# BBB_Board.net
KiCad netlist of a schematic drawn in Altium Designer
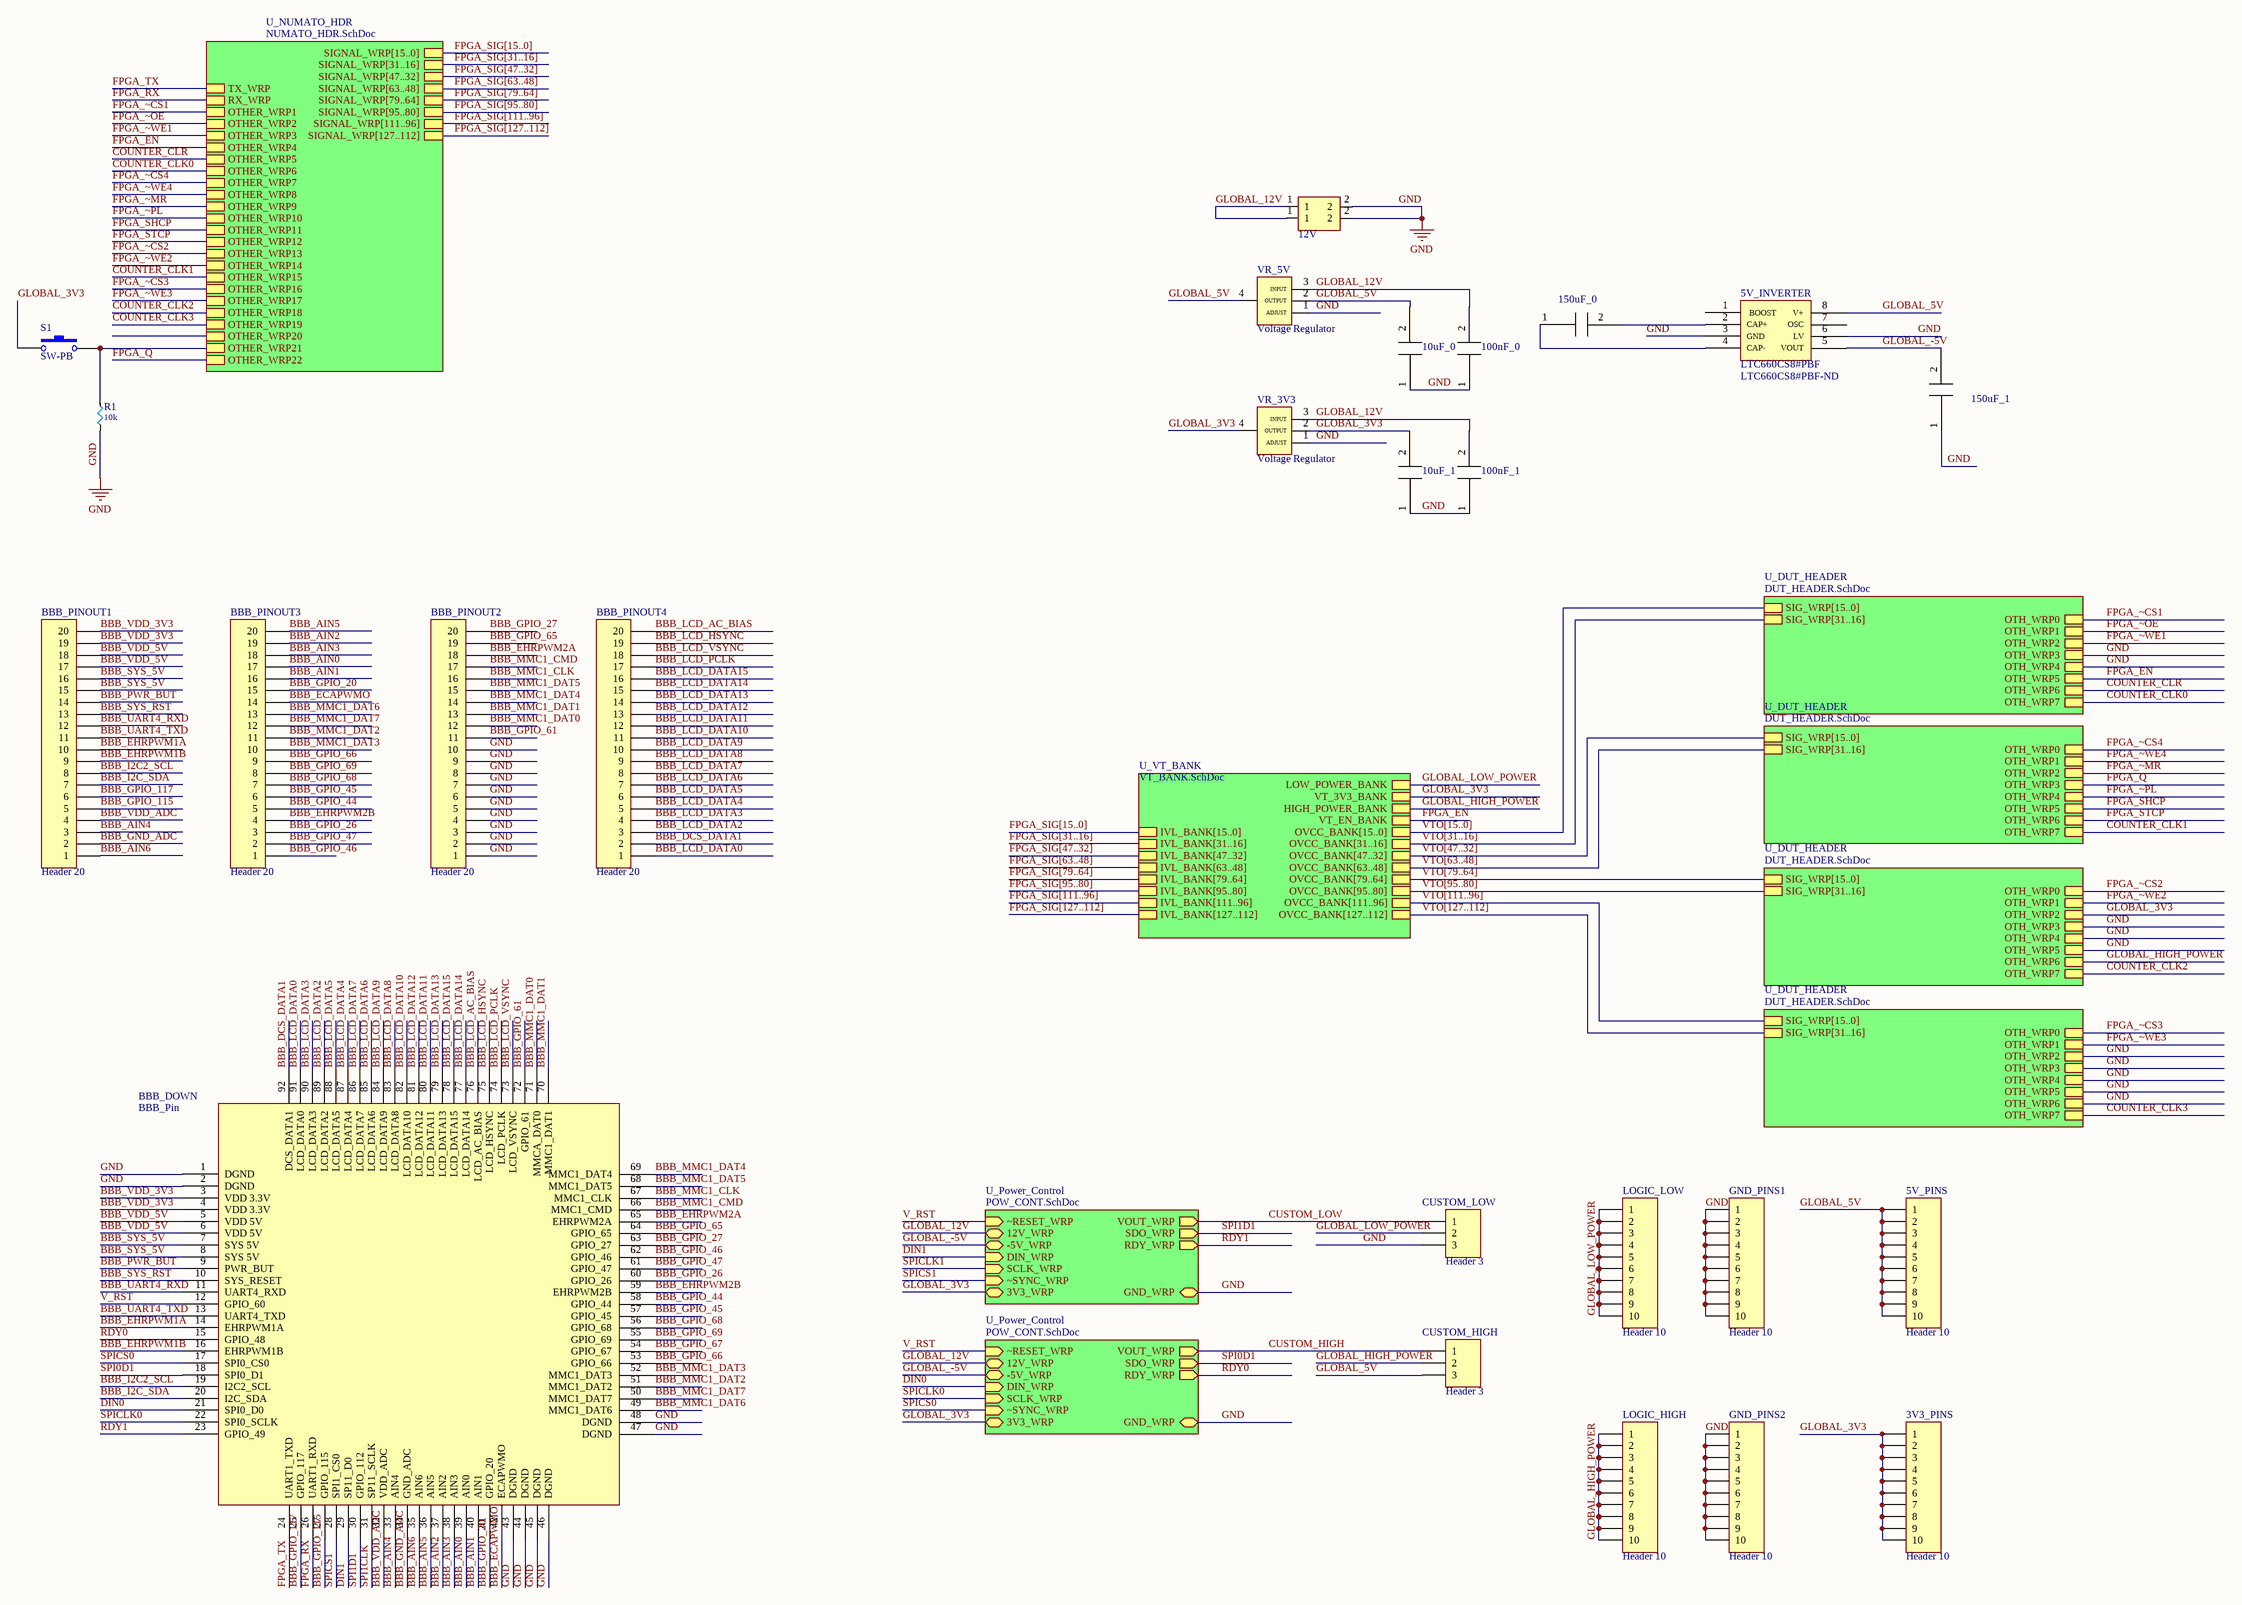
[diagram p0: BBB_Board.SchDoc]

(export (version "E")
  (design (tool "Eeschema 10.0.6"))
  (components
    (comp (ref "3V3_PINS")
      (value "Header 10")
      (footprint "HDR1X10")
      (description "Header, 10-Pin")
      (fields (field (name "PUBLISHER") "Altium Limited"))
      (libsource (lib "Miscellaneous Connectors") (part "Header 10"))
    )
    (comp (ref "5V_INVERTER")
      (value "LTC660CS8#PBF")
      (footprint "SOIC127P600X175-8N")
      (description "IC REG SWTCHD CAP INV 0.1A 8SOIC")
      (fields
        (field (name "MANUFACTURER") "Linear Technology")
        (field (name "SUPPLIER PART NUMBER 1") "LTC660CS8#PBF-ND")
      )
      (libsource (lib "BBB_Board") (part "LTC660CS8#PBF"))
    )
    (comp (ref "5V_PINS")
      (value "Header 10")
      (footprint "HDR1X10")
      (description "Header, 10-Pin")
      (fields (field (name "PUBLISHER") "Altium Limited"))
      (libsource (lib "Miscellaneous Connectors") (part "Header 10"))
    )
    (comp (ref "10uF_0")
      (value "0.1uF_0603")
      (footprint "0.1uF_0603")
      (libsource (lib "BBB_Board") (part "0.1uF_0603"))
    )
    (comp (ref "10uF_1")
      (value "0.1uF_0603")
      (footprint "0.1uF_0603")
      (libsource (lib "BBB_Board") (part "0.1uF_0603"))
    )
    (comp (ref "12V")
      (value "PJ-002BH-SMT-TR")
      (footprint "CP-002BHPJCT-ND")
      (description "CONN POWER JACK 2.5X5.5MM HI CUR")
      (fields (field (name "MANUFACTURER") "CUI Inc"))
      (libsource (lib "BBB_Board") (part "PJ-002BH-SMT-TR"))
    )
    (comp (ref "100nF_0")
      (value "0.1uF_0603")
      (footprint "0.1uF_0603")
      (libsource (lib "BBB_Board") (part "0.1uF_0603"))
    )
    (comp (ref "100nF_1")
      (value "0.1uF_0603")
      (footprint "0.1uF_0603")
      (libsource (lib "BBB_Board") (part "0.1uF_0603"))
    )
    (comp (ref "150uF_0")
      (value "0.1uF_0603")
      (footprint "0.1uF_0603")
      (libsource (lib "BBB_Board") (part "0.1uF_0603"))
    )
    (comp (ref "150uF_1")
      (value "0.1uF_0603")
      (footprint "0.1uF_0603")
      (libsource (lib "BBB_Board") (part "0.1uF_0603"))
    )
    (comp (ref "BBB_DOWN")
      (value "BBB_Pin")
      (footprint "BBB_Pin")
      (libsource (lib "BBB_Board") (part "BBB_Pin"))
    )
    (comp (ref "BBB_PINOUT1")
      (value "Header 20")
      (footprint "HDR1X20")
      (description "Header, 20-Pin")
      (fields (field (name "PUBLISHER") "Altium Limited"))
      (libsource (lib "Miscellaneous Connectors") (part "Header 20"))
    )
    (comp (ref "BBB_PINOUT2")
      (value "Header 20")
      (footprint "HDR1X20")
      (description "Header, 20-Pin")
      (fields (field (name "PUBLISHER") "Altium Limited"))
      (libsource (lib "Miscellaneous Connectors") (part "Header 20"))
    )
    (comp (ref "BBB_PINOUT3")
      (value "Header 20")
      (footprint "HDR1X20")
      (description "Header, 20-Pin")
      (fields (field (name "PUBLISHER") "Altium Limited"))
      (libsource (lib "Miscellaneous Connectors") (part "Header 20"))
    )
    (comp (ref "BBB_PINOUT4")
      (value "Header 20")
      (footprint "HDR1X20")
      (description "Header, 20-Pin")
      (fields (field (name "PUBLISHER") "Altium Limited"))
      (libsource (lib "Miscellaneous Connectors") (part "Header 20"))
    )
    (comp (ref "CUSTOM_HIGH")
      (value "Header 3")
      (footprint "HDR1X3")
      (description "Header, 3-Pin")
      (fields (field (name "PUBLISHER") "Altium Limited"))
      (libsource (lib "Miscellaneous Connectors") (part "Header 3"))
    )
    (comp (ref "CUSTOM_LOW")
      (value "Header 3")
      (footprint "HDR1X3")
      (description "Header, 3-Pin")
      (fields (field (name "PUBLISHER") "Altium Limited"))
      (libsource (lib "Miscellaneous Connectors") (part "Header 3"))
    )
    (comp (ref "GND_PINS1")
      (value "Header 10")
      (footprint "HDR1X10")
      (description "Header, 10-Pin")
      (fields (field (name "PUBLISHER") "Altium Limited"))
      (libsource (lib "Miscellaneous Connectors") (part "Header 10"))
    )
    (comp (ref "GND_PINS2")
      (value "Header 10")
      (footprint "HDR1X10")
      (description "Header, 10-Pin")
      (fields (field (name "PUBLISHER") "Altium Limited"))
      (libsource (lib "Miscellaneous Connectors") (part "Header 10"))
    )
    (comp (ref "LOGIC_HIGH")
      (value "Header 10")
      (footprint "HDR1X10")
      (description "Header, 10-Pin")
      (fields (field (name "PUBLISHER") "Altium Limited"))
      (libsource (lib "Miscellaneous Connectors") (part "Header 10"))
    )
    (comp (ref "LOGIC_LOW")
      (value "Header 10")
      (footprint "HDR1X10")
      (description "Header, 10-Pin")
      (fields (field (name "PUBLISHER") "Altium Limited"))
      (libsource (lib "Miscellaneous Connectors") (part "Header 10"))
    )
    (comp (ref "R1")
      (value "RNCS0603BKE10K0")
      (footprint "0.1uF_0603")
      (description "RES 10K OHM 1/16W 0.1% 0603")
      (fields
        (field (name "MANUFACTURER") "Stackpole Electronics Inc")
        (field (name "TOLERANCE") "±0.1%")
        (field (name "RESISTANCE (OHMS)") "10k")
      )
      (libsource (lib "BBB_Board") (part "RNCS0603BKE10K0"))
    )
    (comp (ref "S1")
      (value "SW-PB")
      (footprint "SPST-2")
      (description "Switch")
      (fields (field (name "PUBLISHER") "Altium Limited"))
      (libsource (lib "Miscellaneous Devices") (part "SW-PB"))
    )
    (comp (ref "VR_3V3")
      (value "Voltage Regulator")
      (footprint "volt_reg")
      (description "IC REG LDO ADJ 1.5A DDPAK")
      (fields
        (field (name "MANUFACTURER") "Texas Instruments")
        (field (name "MANUFACTURER PART NUMBER") "LM317KTTR")
      )
      (libsource (lib "BBB_Board") (part "Voltage Regulator"))
    )
    (comp (ref "VR_5V")
      (value "Voltage Regulator")
      (footprint "volt_reg")
      (description "IC REG LDO ADJ 1.5A DDPAK")
      (fields
        (field (name "MANUFACTURER") "Texas Instruments")
        (field (name "MANUFACTURER PART NUMBER") "LM317KTTR")
      )
      (libsource (lib "BBB_Board") (part "Voltage Regulator"))
    )
  )
  (nets
    (net (code "257") (name "/BBB_AIN0") (class "Default")
      (node (ref "BBB_DOWN") (pin "39") (pinfunction "AIN0_39") (pintype "passive"))
      (node (ref "BBB_PINOUT3") (pin "17") (pinfunction "17_17") (pintype "passive"))
    )
    (net (code "258") (name "/BBB_AIN1") (class "Default")
      (node (ref "BBB_DOWN") (pin "40") (pinfunction "AIN1_40") (pintype "passive"))
      (node (ref "BBB_PINOUT3") (pin "16") (pinfunction "16_16") (pintype "passive"))
    )
    (net (code "259") (name "/BBB_AIN2") (class "Default")
      (node (ref "BBB_DOWN") (pin "37") (pinfunction "AIN2_37") (pintype "passive"))
      (node (ref "BBB_PINOUT3") (pin "19") (pinfunction "19_19") (pintype "passive"))
    )
    (net (code "260") (name "/BBB_AIN3") (class "Default")
      (node (ref "BBB_DOWN") (pin "38") (pinfunction "AIN3_38") (pintype "passive"))
      (node (ref "BBB_PINOUT3") (pin "18") (pinfunction "18_18") (pintype "passive"))
    )
    (net (code "261") (name "/BBB_AIN4") (class "Default")
      (node (ref "BBB_DOWN") (pin "33") (pinfunction "AIN4_33") (pintype "passive"))
      (node (ref "BBB_PINOUT1") (pin "3") (pinfunction "3_3") (pintype "passive"))
    )
    (net (code "262") (name "/BBB_AIN5") (class "Default")
      (node (ref "BBB_DOWN") (pin "36") (pinfunction "AIN5_36") (pintype "passive"))
      (node (ref "BBB_PINOUT3") (pin "20") (pinfunction "20_20") (pintype "passive"))
    )
    (net (code "263") (name "/BBB_AIN6") (class "Default")
      (node (ref "BBB_DOWN") (pin "35") (pinfunction "AIN6_35") (pintype "passive"))
      (node (ref "BBB_PINOUT1") (pin "1") (pinfunction "1_1") (pintype "passive"))
    )
    (net (code "264") (name "/BBB_DCS_DATA1") (class "Default")
      (node (ref "BBB_DOWN") (pin "92") (pinfunction "DCS_DATA1_92") (pintype "passive"))
      (node (ref "BBB_PINOUT4") (pin "2") (pinfunction "2_2") (pintype "passive"))
    )
    (net (code "265") (name "/BBB_ECAPWMO") (class "Default")
      (node (ref "BBB_DOWN") (pin "42") (pinfunction "ECAPWMO_42") (pintype "passive"))
      (node (ref "BBB_PINOUT3") (pin "14") (pinfunction "14_14") (pintype "passive"))
    )
    (net (code "266") (name "/BBB_EHRPWM1A") (class "Default")
      (node (ref "BBB_DOWN") (pin "14") (pinfunction "EHRPWM1A_14") (pintype "passive"))
      (node (ref "BBB_PINOUT1") (pin "10") (pinfunction "10_10") (pintype "passive"))
    )
    (net (code "267") (name "/BBB_EHRPWM1B") (class "Default")
      (node (ref "BBB_DOWN") (pin "16") (pinfunction "EHRPWM1B_16") (pintype "passive"))
      (node (ref "BBB_PINOUT1") (pin "9") (pinfunction "9_9") (pintype "passive"))
    )
    (net (code "268") (name "/BBB_EHRPWM2A") (class "Default")
      (node (ref "BBB_DOWN") (pin "65") (pinfunction "EHRPWM2A_65") (pintype "passive"))
      (node (ref "BBB_PINOUT2") (pin "18") (pinfunction "18_18") (pintype "passive"))
    )
    (net (code "269") (name "/BBB_EHRPWM2B") (class "Default")
      (node (ref "BBB_DOWN") (pin "59") (pinfunction "EHRPWM2B_59") (pintype "passive"))
      (node (ref "BBB_PINOUT3") (pin "4") (pinfunction "4_4") (pintype "passive"))
    )
    (net (code "270") (name "/BBB_GND_ADC") (class "Default")
      (node (ref "BBB_DOWN") (pin "34") (pinfunction "GND_ADC_34") (pintype "passive"))
      (node (ref "BBB_PINOUT1") (pin "2") (pinfunction "2_2") (pintype "passive"))
    )
    (net (code "271") (name "/BBB_GPIO_20") (class "Default")
      (node (ref "BBB_DOWN") (pin "41") (pinfunction "GPIO_20_41") (pintype "passive"))
      (node (ref "BBB_PINOUT3") (pin "15") (pinfunction "15_15") (pintype "passive"))
    )
    (net (code "272") (name "/BBB_GPIO_26") (class "Default")
      (node (ref "BBB_DOWN") (pin "60") (pinfunction "GPIO_26_60") (pintype "passive"))
      (node (ref "BBB_PINOUT3") (pin "3") (pinfunction "3_3") (pintype "passive"))
    )
    (net (code "273") (name "/BBB_GPIO_27") (class "Default")
      (node (ref "BBB_DOWN") (pin "63") (pinfunction "GPIO_27_63") (pintype "passive"))
      (node (ref "BBB_PINOUT2") (pin "20") (pinfunction "20_20") (pintype "passive"))
    )
    (net (code "274") (name "/BBB_GPIO_44") (class "Default")
      (node (ref "BBB_DOWN") (pin "58") (pinfunction "GPIO_44_58") (pintype "passive"))
      (node (ref "BBB_PINOUT3") (pin "5") (pinfunction "5_5") (pintype "passive"))
    )
    (net (code "275") (name "/BBB_GPIO_45") (class "Default")
      (node (ref "BBB_DOWN") (pin "57") (pinfunction "GPIO_45_57") (pintype "passive"))
      (node (ref "BBB_PINOUT3") (pin "6") (pinfunction "6_6") (pintype "passive"))
    )
    (net (code "276") (name "/BBB_GPIO_46") (class "Default")
      (node (ref "BBB_DOWN") (pin "62") (pinfunction "GPIO_46_62") (pintype "passive"))
      (node (ref "BBB_PINOUT3") (pin "1") (pinfunction "1_1") (pintype "passive"))
    )
    (net (code "277") (name "/BBB_GPIO_47") (class "Default")
      (node (ref "BBB_DOWN") (pin "61") (pinfunction "GPIO_47_61") (pintype "passive"))
      (node (ref "BBB_PINOUT3") (pin "2") (pinfunction "2_2") (pintype "passive"))
    )
    (net (code "278") (name "/BBB_GPIO_61") (class "Default")
      (node (ref "BBB_DOWN") (pin "72") (pinfunction "GPIO_61_72") (pintype "passive"))
      (node (ref "BBB_PINOUT2") (pin "11") (pinfunction "11_11") (pintype "passive"))
    )
    (net (code "279") (name "/BBB_GPIO_65") (class "Default")
      (node (ref "BBB_DOWN") (pin "64") (pinfunction "GPIO_65_64") (pintype "passive"))
      (node (ref "BBB_PINOUT2") (pin "19") (pinfunction "19_19") (pintype "passive"))
    )
    (net (code "280") (name "/BBB_GPIO_66") (class "Default")
      (node (ref "BBB_DOWN") (pin "53") (pinfunction "GPIO_66_53") (pintype "passive"))
      (node (ref "BBB_PINOUT3") (pin "9") (pinfunction "9_9") (pintype "passive"))
    )
    (net (code "281") (name "/BBB_GPIO_67") (class "Default")
      (node (ref "BBB_DOWN") (pin "54") (pinfunction "GPIO_67_54") (pintype "passive"))
    )
    (net (code "282") (name "/BBB_GPIO_68") (class "Default")
      (node (ref "BBB_DOWN") (pin "56") (pinfunction "GPIO_68_56") (pintype "passive"))
      (node (ref "BBB_PINOUT3") (pin "7") (pinfunction "7_7") (pintype "passive"))
    )
    (net (code "283") (name "/BBB_GPIO_69") (class "Default")
      (node (ref "BBB_DOWN") (pin "55") (pinfunction "GPIO_69_55") (pintype "passive"))
      (node (ref "BBB_PINOUT3") (pin "8") (pinfunction "8_8") (pintype "passive"))
    )
    (net (code "284") (name "/BBB_GPIO_115") (class "Default")
      (node (ref "BBB_DOWN") (pin "27") (pinfunction "GPIO_115_27") (pintype "passive"))
      (node (ref "BBB_PINOUT1") (pin "5") (pinfunction "5_5") (pintype "passive"))
    )
    (net (code "285") (name "/BBB_GPIO_117") (class "Default")
      (node (ref "BBB_DOWN") (pin "25") (pinfunction "GPIO_117_25") (pintype "passive"))
      (node (ref "BBB_PINOUT1") (pin "6") (pinfunction "6_6") (pintype "passive"))
    )
    (net (code "286") (name "/BBB_I2C2_SCL") (class "Default")
      (node (ref "BBB_DOWN") (pin "19") (pinfunction "I2C2_SCL_19") (pintype "passive"))
      (node (ref "BBB_PINOUT1") (pin "8") (pinfunction "8_8") (pintype "passive"))
    )
    (net (code "287") (name "/BBB_I2C_SDA") (class "Default")
      (node (ref "BBB_DOWN") (pin "20") (pinfunction "I2C_SDA_20") (pintype "passive"))
      (node (ref "BBB_PINOUT1") (pin "7") (pinfunction "7_7") (pintype "passive"))
    )
    (net (code "288") (name "/BBB_LCD_AC_BIAS") (class "Default")
      (node (ref "BBB_DOWN") (pin "76") (pinfunction "LCD_AC_BIAS_76") (pintype "passive"))
      (node (ref "BBB_PINOUT4") (pin "20") (pinfunction "20_20") (pintype "passive"))
    )
    (net (code "289") (name "/BBB_LCD_DATA0") (class "Default")
      (node (ref "BBB_DOWN") (pin "91") (pinfunction "LCD_DATA0_91") (pintype "passive"))
      (node (ref "BBB_PINOUT4") (pin "1") (pinfunction "1_1") (pintype "passive"))
    )
    (net (code "290") (name "/BBB_LCD_DATA2") (class "Default")
      (node (ref "BBB_DOWN") (pin "89") (pinfunction "LCD_DATA2_89") (pintype "passive"))
      (node (ref "BBB_PINOUT4") (pin "3") (pinfunction "3_3") (pintype "passive"))
    )
    (net (code "291") (name "/BBB_LCD_DATA3") (class "Default")
      (node (ref "BBB_DOWN") (pin "90") (pinfunction "LCD_DATA3_90") (pintype "passive"))
      (node (ref "BBB_PINOUT4") (pin "4") (pinfunction "4_4") (pintype "passive"))
    )
    (net (code "292") (name "/BBB_LCD_DATA4") (class "Default")
      (node (ref "BBB_DOWN") (pin "87") (pinfunction "LCD_DATA4_87") (pintype "passive"))
      (node (ref "BBB_PINOUT4") (pin "5") (pinfunction "5_5") (pintype "passive"))
    )
    (net (code "293") (name "/BBB_LCD_DATA5") (class "Default")
      (node (ref "BBB_DOWN") (pin "88") (pinfunction "LCD_DATA5_88") (pintype "passive"))
      (node (ref "BBB_PINOUT4") (pin "6") (pinfunction "6_6") (pintype "passive"))
    )
    (net (code "294") (name "/BBB_LCD_DATA6") (class "Default")
      (node (ref "BBB_DOWN") (pin "85") (pinfunction "LCD_DATA6_85") (pintype "passive"))
      (node (ref "BBB_PINOUT4") (pin "7") (pinfunction "7_7") (pintype "passive"))
    )
    (net (code "295") (name "/BBB_LCD_DATA7") (class "Default")
      (node (ref "BBB_DOWN") (pin "86") (pinfunction "LCD_DATA7_86") (pintype "passive"))
      (node (ref "BBB_PINOUT4") (pin "8") (pinfunction "8_8") (pintype "passive"))
    )
    (net (code "296") (name "/BBB_LCD_DATA8") (class "Default")
      (node (ref "BBB_DOWN") (pin "83") (pinfunction "LCD_DATA8_83") (pintype "passive"))
      (node (ref "BBB_PINOUT4") (pin "9") (pinfunction "9_9") (pintype "passive"))
    )
    (net (code "297") (name "/BBB_LCD_DATA9") (class "Default")
      (node (ref "BBB_DOWN") (pin "84") (pinfunction "LCD_DATA9_84") (pintype "passive"))
      (node (ref "BBB_PINOUT4") (pin "10") (pinfunction "10_10") (pintype "passive"))
    )
    (net (code "298") (name "/BBB_LCD_DATA10") (class "Default")
      (node (ref "BBB_DOWN") (pin "82") (pinfunction "LCD_DATA10_82") (pintype "passive"))
      (node (ref "BBB_PINOUT4") (pin "11") (pinfunction "11_11") (pintype "passive"))
    )
    (net (code "299") (name "/BBB_LCD_DATA11") (class "Default")
      (node (ref "BBB_DOWN") (pin "80") (pinfunction "LCD_DATA11_80") (pintype "passive"))
      (node (ref "BBB_PINOUT4") (pin "12") (pinfunction "12_12") (pintype "passive"))
    )
    (net (code "300") (name "/BBB_LCD_DATA12") (class "Default")
      (node (ref "BBB_DOWN") (pin "81") (pinfunction "LCD_DATA12_81") (pintype "passive"))
      (node (ref "BBB_PINOUT4") (pin "13") (pinfunction "13_13") (pintype "passive"))
    )
    (net (code "301") (name "/BBB_LCD_DATA13") (class "Default")
      (node (ref "BBB_DOWN") (pin "79") (pinfunction "LCD_DATA13_79") (pintype "passive"))
      (node (ref "BBB_PINOUT4") (pin "14") (pinfunction "14_14") (pintype "passive"))
    )
    (net (code "302") (name "/BBB_LCD_DATA14") (class "Default")
      (node (ref "BBB_DOWN") (pin "77") (pinfunction "LCD_DATA14_77") (pintype "passive"))
      (node (ref "BBB_PINOUT4") (pin "15") (pinfunction "15_15") (pintype "passive"))
    )
    (net (code "303") (name "/BBB_LCD_DATA15") (class "Default")
      (node (ref "BBB_DOWN") (pin "78") (pinfunction "LCD_DATA15_78") (pintype "passive"))
      (node (ref "BBB_PINOUT4") (pin "16") (pinfunction "16_16") (pintype "passive"))
    )
    (net (code "304") (name "/BBB_LCD_HSYNC") (class "Default")
      (node (ref "BBB_DOWN") (pin "75") (pinfunction "LCD_HSYNC_75") (pintype "passive"))
      (node (ref "BBB_PINOUT4") (pin "19") (pinfunction "19_19") (pintype "passive"))
    )
    (net (code "305") (name "/BBB_LCD_PCLK") (class "Default")
      (node (ref "BBB_DOWN") (pin "74") (pinfunction "LCD_PCLK_74") (pintype "passive"))
      (node (ref "BBB_PINOUT4") (pin "17") (pinfunction "17_17") (pintype "passive"))
    )
    (net (code "306") (name "/BBB_LCD_VSYNC") (class "Default")
      (node (ref "BBB_DOWN") (pin "73") (pinfunction "LCD_VSYNC_73") (pintype "passive"))
      (node (ref "BBB_PINOUT4") (pin "18") (pinfunction "18_18") (pintype "passive"))
    )
    (net (code "307") (name "/BBB_MMC1_CLK") (class "Default")
      (node (ref "BBB_DOWN") (pin "67") (pinfunction "MMC1_CLK_67") (pintype "passive"))
      (node (ref "BBB_PINOUT2") (pin "16") (pinfunction "16_16") (pintype "passive"))
    )
    (net (code "308") (name "/BBB_MMC1_CMD") (class "Default")
      (node (ref "BBB_DOWN") (pin "66") (pinfunction "MMC1_CMD_66") (pintype "passive"))
      (node (ref "BBB_PINOUT2") (pin "17") (pinfunction "17_17") (pintype "passive"))
    )
    (net (code "309") (name "/BBB_MMC1_DAT0") (class "Default")
      (node (ref "BBB_DOWN") (pin "71") (pinfunction "MMCA_DAT0_71") (pintype "passive"))
      (node (ref "BBB_PINOUT2") (pin "12") (pinfunction "12_12") (pintype "passive"))
    )
    (net (code "310") (name "/BBB_MMC1_DAT1") (class "Default")
      (node (ref "BBB_DOWN") (pin "70") (pinfunction "MMC1_DAT1_70") (pintype "passive"))
      (node (ref "BBB_PINOUT2") (pin "13") (pinfunction "13_13") (pintype "passive"))
    )
    (net (code "311") (name "/BBB_MMC1_DAT2") (class "Default")
      (node (ref "BBB_DOWN") (pin "51") (pinfunction "MMC1_DAT2_51") (pintype "passive"))
      (node (ref "BBB_PINOUT3") (pin "11") (pinfunction "11_11") (pintype "passive"))
    )
    (net (code "312") (name "/BBB_MMC1_DAT3") (class "Default")
      (node (ref "BBB_DOWN") (pin "52") (pinfunction "MMC1_DAT3_52") (pintype "passive"))
      (node (ref "BBB_PINOUT3") (pin "10") (pinfunction "10_10") (pintype "passive"))
    )
    (net (code "313") (name "/BBB_MMC1_DAT4") (class "Default")
      (node (ref "BBB_DOWN") (pin "69") (pinfunction "MMC1_DAT4_69") (pintype "passive"))
      (node (ref "BBB_PINOUT2") (pin "14") (pinfunction "14_14") (pintype "passive"))
    )
    (net (code "314") (name "/BBB_MMC1_DAT5") (class "Default")
      (node (ref "BBB_DOWN") (pin "68") (pinfunction "MMC1_DAT5_68") (pintype "passive"))
      (node (ref "BBB_PINOUT2") (pin "15") (pinfunction "15_15") (pintype "passive"))
    )
    (net (code "315") (name "/BBB_MMC1_DAT6") (class "Default")
      (node (ref "BBB_DOWN") (pin "49") (pinfunction "MMC1_DAT6_49") (pintype "passive"))
      (node (ref "BBB_PINOUT3") (pin "13") (pinfunction "13_13") (pintype "passive"))
    )
    (net (code "316") (name "/BBB_MMC1_DAT7") (class "Default")
      (node (ref "BBB_DOWN") (pin "50") (pinfunction "MMC1_DAT7_50") (pintype "passive"))
      (node (ref "BBB_PINOUT3") (pin "12") (pinfunction "12_12") (pintype "passive"))
    )
    (net (code "317") (name "/BBB_PWR_BUT") (class "Default")
      (node (ref "BBB_DOWN") (pin "9") (pinfunction "PWR_BUT_9") (pintype "passive"))
      (node (ref "BBB_PINOUT1") (pin "14") (pinfunction "14_14") (pintype "passive"))
    )
    (net (code "318") (name "/BBB_SYS_5V") (class "Default")
      (node (ref "BBB_DOWN") (pin "7") (pinfunction "SYS_5V_7") (pintype "passive"))
      (node (ref "BBB_DOWN") (pin "8") (pinfunction "SYS_5V_8") (pintype "passive"))
      (node (ref "BBB_PINOUT1") (pin "15") (pinfunction "15_15") (pintype "passive"))
      (node (ref "BBB_PINOUT1") (pin "16") (pinfunction "16_16") (pintype "passive"))
    )
    (net (code "319") (name "/BBB_SYS_RST") (class "Default")
      (node (ref "BBB_DOWN") (pin "10") (pinfunction "SYS_RESET_10") (pintype "passive"))
      (node (ref "BBB_PINOUT1") (pin "13") (pinfunction "13_13") (pintype "passive"))
    )
    (net (code "320") (name "/BBB_UART4_RXD") (class "Default")
      (node (ref "BBB_DOWN") (pin "11") (pinfunction "UART4_RXD_11") (pintype "passive"))
      (node (ref "BBB_PINOUT1") (pin "12") (pinfunction "12_12") (pintype "passive"))
    )
    (net (code "321") (name "/BBB_UART4_TXD") (class "Default")
      (node (ref "BBB_DOWN") (pin "13") (pinfunction "UART4_TXD_13") (pintype "passive"))
      (node (ref "BBB_PINOUT1") (pin "11") (pinfunction "11_11") (pintype "passive"))
    )
    (net (code "322") (name "/BBB_VDD_3V3") (class "Default")
      (node (ref "BBB_DOWN") (pin "3") (pinfunction "VDD_3.3V_3") (pintype "passive"))
      (node (ref "BBB_DOWN") (pin "4") (pinfunction "VDD_3.3V_4") (pintype "passive"))
      (node (ref "BBB_PINOUT1") (pin "19") (pinfunction "19_19") (pintype "passive"))
      (node (ref "BBB_PINOUT1") (pin "20") (pinfunction "20_20") (pintype "passive"))
    )
    (net (code "323") (name "/BBB_VDD_5V") (class "Default")
      (node (ref "BBB_DOWN") (pin "5") (pinfunction "VDD_5V_5") (pintype "passive"))
      (node (ref "BBB_DOWN") (pin "6") (pinfunction "VDD_5V_6") (pintype "passive"))
      (node (ref "BBB_PINOUT1") (pin "17") (pinfunction "17_17") (pintype "passive"))
      (node (ref "BBB_PINOUT1") (pin "18") (pinfunction "18_18") (pintype "passive"))
    )
    (net (code "324") (name "/BBB_VDD_ADC") (class "Default")
      (node (ref "BBB_DOWN") (pin "32") (pinfunction "VDD_ADC_32") (pintype "passive"))
      (node (ref "BBB_PINOUT1") (pin "4") (pinfunction "4_4") (pintype "passive"))
    )
    (net (code "330") (name "/CUSTOM_HIGH") (class "Default")
      (node (ref "CUSTOM_HIGH") (pin "1") (pinfunction "1_1") (pintype "passive"))
    )
    (net (code "331") (name "/CUSTOM_LOW") (class "Default")
      (node (ref "CUSTOM_LOW") (pin "1") (pinfunction "1_1") (pintype "passive"))
    )
    (net (code "332") (name "/DIN0") (class "Default")
      (node (ref "BBB_DOWN") (pin "21") (pinfunction "SPI0_D0_21") (pintype "passive"))
    )
    (net (code "333") (name "/DIN1") (class "Default")
      (node (ref "BBB_DOWN") (pin "29") (pinfunction "SP11_D0_29") (pintype "passive"))
    )
    (net (code "336") (name "/FPGA_RX") (class "Default")
      (node (ref "BBB_DOWN") (pin "26") (pinfunction "UART1_RXD_26") (pintype "passive"))
    )
    (net (code "347") (name "/FPGA_TX") (class "Default")
      (node (ref "BBB_DOWN") (pin "24") (pinfunction "UART1_TXD_24") (pintype "passive"))
    )
    (net (code "359") (name "/GLOBAL_-5V") (class "Default")
      (node (ref "150uF_1") (pin "2") (pinfunction "2_2") (pintype "passive"))
      (node (ref "5V_INVERTER") (pin "5") (pinfunction "VOUT_5") (pintype "passive"))
    )
    (net (code "360") (name "/GLOBAL_3V3") (class "Default")
      (node (ref "10uF_1") (pin "2") (pinfunction "2_2") (pintype "passive"))
      (node (ref "3V3_PINS") (pin "1") (pinfunction "1_1") (pintype "passive"))
      (node (ref "3V3_PINS") (pin "10") (pinfunction "10_10") (pintype "passive"))
      (node (ref "3V3_PINS") (pin "2") (pinfunction "2_2") (pintype "passive"))
      (node (ref "3V3_PINS") (pin "3") (pinfunction "3_3") (pintype "passive"))
      (node (ref "3V3_PINS") (pin "4") (pinfunction "4_4") (pintype "passive"))
      (node (ref "3V3_PINS") (pin "5") (pinfunction "5_5") (pintype "passive"))
      (node (ref "3V3_PINS") (pin "6") (pinfunction "6_6") (pintype "passive"))
      (node (ref "3V3_PINS") (pin "7") (pinfunction "7_7") (pintype "passive"))
      (node (ref "3V3_PINS") (pin "8") (pinfunction "8_8") (pintype "passive"))
      (node (ref "3V3_PINS") (pin "9") (pinfunction "9_9") (pintype "passive"))
      (node (ref "S1") (pin "1") (pinfunction "1_1") (pintype "passive"))
      (node (ref "VR_3V3") (pin "2") (pinfunction "OUTPUT_2") (pintype "passive"))
      (node (ref "VR_3V3") (pin "4") (pinfunction "Output_4") (pintype "passive"))
    )
    (net (code "361") (name "/GLOBAL_5V") (class "Default")
      (node (ref "10uF_0") (pin "2") (pinfunction "2_2") (pintype "passive"))
      (node (ref "5V_INVERTER") (pin "8") (pinfunction "V+_8") (pintype "passive"))
      (node (ref "5V_PINS") (pin "1") (pinfunction "1_1") (pintype "passive"))
      (node (ref "5V_PINS") (pin "10") (pinfunction "10_10") (pintype "passive"))
      (node (ref "5V_PINS") (pin "2") (pinfunction "2_2") (pintype "passive"))
      (node (ref "5V_PINS") (pin "3") (pinfunction "3_3") (pintype "passive"))
      (node (ref "5V_PINS") (pin "4") (pinfunction "4_4") (pintype "passive"))
      (node (ref "5V_PINS") (pin "5") (pinfunction "5_5") (pintype "passive"))
      (node (ref "5V_PINS") (pin "6") (pinfunction "6_6") (pintype "passive"))
      (node (ref "5V_PINS") (pin "7") (pinfunction "7_7") (pintype "passive"))
      (node (ref "5V_PINS") (pin "8") (pinfunction "8_8") (pintype "passive"))
      (node (ref "5V_PINS") (pin "9") (pinfunction "9_9") (pintype "passive"))
      (node (ref "CUSTOM_HIGH") (pin "3") (pinfunction "3_3") (pintype "passive"))
      (node (ref "VR_5V") (pin "2") (pinfunction "OUTPUT_2") (pintype "passive"))
      (node (ref "VR_5V") (pin "4") (pinfunction "Output_4") (pintype "passive"))
    )
    (net (code "362") (name "/GLOBAL_12V") (class "Default")
      (node (ref "100nF_0") (pin "2") (pinfunction "2_2") (pintype "passive"))
      (node (ref "100nF_1") (pin "2") (pinfunction "2_2") (pintype "passive"))
      (node (ref "12V") (pin "1") (pinfunction "1_1") (pintype "passive"))
      (node (ref "VR_3V3") (pin "3") (pinfunction "INPUT_3") (pintype "passive"))
      (node (ref "VR_5V") (pin "3") (pinfunction "INPUT_3") (pintype "passive"))
    )
    (net (code "363") (name "/GLOBAL_HIGH_POWER") (class "Default")
      (node (ref "CUSTOM_HIGH") (pin "2") (pinfunction "2_2") (pintype "passive"))
      (node (ref "LOGIC_HIGH") (pin "1") (pinfunction "1_1") (pintype "passive"))
      (node (ref "LOGIC_HIGH") (pin "10") (pinfunction "10_10") (pintype "passive"))
      (node (ref "LOGIC_HIGH") (pin "2") (pinfunction "2_2") (pintype "passive"))
      (node (ref "LOGIC_HIGH") (pin "3") (pinfunction "3_3") (pintype "passive"))
      (node (ref "LOGIC_HIGH") (pin "4") (pinfunction "4_4") (pintype "passive"))
      (node (ref "LOGIC_HIGH") (pin "5") (pinfunction "5_5") (pintype "passive"))
      (node (ref "LOGIC_HIGH") (pin "6") (pinfunction "6_6") (pintype "passive"))
      (node (ref "LOGIC_HIGH") (pin "7") (pinfunction "7_7") (pintype "passive"))
      (node (ref "LOGIC_HIGH") (pin "8") (pinfunction "8_8") (pintype "passive"))
      (node (ref "LOGIC_HIGH") (pin "9") (pinfunction "9_9") (pintype "passive"))
    )
    (net (code "364") (name "/GLOBAL_LOW_POWER") (class "Default")
      (node (ref "CUSTOM_LOW") (pin "2") (pinfunction "2_2") (pintype "passive"))
      (node (ref "LOGIC_LOW") (pin "1") (pinfunction "1_1") (pintype "passive"))
      (node (ref "LOGIC_LOW") (pin "10") (pinfunction "10_10") (pintype "passive"))
      (node (ref "LOGIC_LOW") (pin "2") (pinfunction "2_2") (pintype "passive"))
      (node (ref "LOGIC_LOW") (pin "3") (pinfunction "3_3") (pintype "passive"))
      (node (ref "LOGIC_LOW") (pin "4") (pinfunction "4_4") (pintype "passive"))
      (node (ref "LOGIC_LOW") (pin "5") (pinfunction "5_5") (pintype "passive"))
      (node (ref "LOGIC_LOW") (pin "6") (pinfunction "6_6") (pintype "passive"))
      (node (ref "LOGIC_LOW") (pin "7") (pinfunction "7_7") (pintype "passive"))
      (node (ref "LOGIC_LOW") (pin "8") (pinfunction "8_8") (pintype "passive"))
      (node (ref "LOGIC_LOW") (pin "9") (pinfunction "9_9") (pintype "passive"))
    )
    (net (code "366") (name "/OTHER_WRP21") (class "Default")
      (node (ref "R1") (pin "2") (pinfunction "2_2") (pintype "passive"))
      (node (ref "S1") (pin "2") (pinfunction "2_2") (pintype "passive"))
    )
    (net (code "367") (name "/RDY0") (class "Default")
      (node (ref "BBB_DOWN") (pin "15") (pinfunction "GPIO_48_15") (pintype "passive"))
    )
    (net (code "368") (name "/RDY1") (class "Default")
      (node (ref "BBB_DOWN") (pin "23") (pinfunction "GPIO_49_23") (pintype "passive"))
    )
    (net (code "369") (name "/SPI0D1") (class "Default")
      (node (ref "BBB_DOWN") (pin "18") (pinfunction "SPI0_D1_18") (pintype "passive"))
    )
    (net (code "370") (name "/SPI1CLK") (class "Default")
      (node (ref "BBB_DOWN") (pin "31") (pinfunction "SP11_SCLK_31") (pintype "passive"))
    )
    (net (code "371") (name "/SPI1D1") (class "Default")
      (node (ref "BBB_DOWN") (pin "30") (pinfunction "GPIO_112_30") (pintype "passive"))
    )
    (net (code "372") (name "/SPICLK0") (class "Default")
      (node (ref "BBB_DOWN") (pin "22") (pinfunction "SPI0_SCLK_22") (pintype "passive"))
    )
    (net (code "374") (name "/SPICS0") (class "Default")
      (node (ref "BBB_DOWN") (pin "17") (pinfunction "SPI0_CS0_17") (pintype "passive"))
    )
    (net (code "375") (name "/SPICS1") (class "Default")
      (node (ref "BBB_DOWN") (pin "28") (pinfunction "SPI1_CS0_28") (pintype "passive"))
    )
    (net (code "384") (name "/V_RST") (class "Default")
      (node (ref "BBB_DOWN") (pin "12") (pinfunction "GPIO_60_12") (pintype "passive"))
    )
    (net (code "385") (name "GND") (class "Default")
      (node (ref "100nF_0") (pin "1") (pinfunction "1_1") (pintype "passive"))
      (node (ref "100nF_1") (pin "1") (pinfunction "1_1") (pintype "passive"))
      (node (ref "10uF_0") (pin "1") (pinfunction "1_1") (pintype "passive"))
      (node (ref "10uF_1") (pin "1") (pinfunction "1_1") (pintype "passive"))
      (node (ref "12V") (pin "2") (pinfunction "2_2") (pintype "passive"))
      (node (ref "150uF_1") (pin "1") (pinfunction "1_1") (pintype "passive"))
      (node (ref "5V_INVERTER") (pin "3") (pinfunction "GND_3") (pintype "passive"))
      (node (ref "5V_INVERTER") (pin "6") (pinfunction "LV_6") (pintype "passive"))
      (node (ref "BBB_DOWN") (pin "1") (pinfunction "DGND_1") (pintype "passive"))
      (node (ref "BBB_DOWN") (pin "2") (pinfunction "DGND_2") (pintype "passive"))
      (node (ref "BBB_DOWN") (pin "43") (pinfunction "DGND_43") (pintype "passive"))
      (node (ref "BBB_DOWN") (pin "44") (pinfunction "DGND_44") (pintype "passive"))
      (node (ref "BBB_DOWN") (pin "45") (pinfunction "DGND_45") (pintype "passive"))
      (node (ref "BBB_DOWN") (pin "46") (pinfunction "DGND_46") (pintype "passive"))
      (node (ref "BBB_DOWN") (pin "47") (pinfunction "DGND_47") (pintype "passive"))
      (node (ref "BBB_DOWN") (pin "48") (pinfunction "DGND_48") (pintype "passive"))
      (node (ref "BBB_PINOUT2") (pin "1") (pinfunction "1_1") (pintype "passive"))
      (node (ref "BBB_PINOUT2") (pin "10") (pinfunction "10_10") (pintype "passive"))
      (node (ref "BBB_PINOUT2") (pin "2") (pinfunction "2_2") (pintype "passive"))
      (node (ref "BBB_PINOUT2") (pin "3") (pinfunction "3_3") (pintype "passive"))
      (node (ref "BBB_PINOUT2") (pin "4") (pinfunction "4_4") (pintype "passive"))
      (node (ref "BBB_PINOUT2") (pin "5") (pinfunction "5_5") (pintype "passive"))
      (node (ref "BBB_PINOUT2") (pin "6") (pinfunction "6_6") (pintype "passive"))
      (node (ref "BBB_PINOUT2") (pin "7") (pinfunction "7_7") (pintype "passive"))
      (node (ref "BBB_PINOUT2") (pin "8") (pinfunction "8_8") (pintype "passive"))
      (node (ref "BBB_PINOUT2") (pin "9") (pinfunction "9_9") (pintype "passive"))
      (node (ref "CUSTOM_LOW") (pin "3") (pinfunction "3_3") (pintype "passive"))
      (node (ref "GND_PINS1") (pin "1") (pinfunction "1_1") (pintype "passive"))
      (node (ref "GND_PINS1") (pin "10") (pinfunction "10_10") (pintype "passive"))
      (node (ref "GND_PINS1") (pin "2") (pinfunction "2_2") (pintype "passive"))
      (node (ref "GND_PINS1") (pin "3") (pinfunction "3_3") (pintype "passive"))
      (node (ref "GND_PINS1") (pin "4") (pinfunction "4_4") (pintype "passive"))
      (node (ref "GND_PINS1") (pin "5") (pinfunction "5_5") (pintype "passive"))
      (node (ref "GND_PINS1") (pin "6") (pinfunction "6_6") (pintype "passive"))
      (node (ref "GND_PINS1") (pin "7") (pinfunction "7_7") (pintype "passive"))
      (node (ref "GND_PINS1") (pin "8") (pinfunction "8_8") (pintype "passive"))
      (node (ref "GND_PINS1") (pin "9") (pinfunction "9_9") (pintype "passive"))
      (node (ref "GND_PINS2") (pin "1") (pinfunction "1_1") (pintype "passive"))
      (node (ref "GND_PINS2") (pin "10") (pinfunction "10_10") (pintype "passive"))
      (node (ref "GND_PINS2") (pin "2") (pinfunction "2_2") (pintype "passive"))
      (node (ref "GND_PINS2") (pin "3") (pinfunction "3_3") (pintype "passive"))
      (node (ref "GND_PINS2") (pin "4") (pinfunction "4_4") (pintype "passive"))
      (node (ref "GND_PINS2") (pin "5") (pinfunction "5_5") (pintype "passive"))
      (node (ref "GND_PINS2") (pin "6") (pinfunction "6_6") (pintype "passive"))
      (node (ref "GND_PINS2") (pin "7") (pinfunction "7_7") (pintype "passive"))
      (node (ref "GND_PINS2") (pin "8") (pinfunction "8_8") (pintype "passive"))
      (node (ref "GND_PINS2") (pin "9") (pinfunction "9_9") (pintype "passive"))
      (node (ref "R1") (pin "1") (pinfunction "1_1") (pintype "passive"))
      (node (ref "VR_3V3") (pin "1") (pinfunction "ADJUST_1") (pintype "passive"))
      (node (ref "VR_5V") (pin "1") (pinfunction "ADJUST_1") (pintype "passive"))
    )
    (net (code "386") (name "Net-(5V_INVERTER-CAP+)") (class "Default")
      (node (ref "150uF_0") (pin "2") (pinfunction "2_2") (pintype "passive"))
      (node (ref "5V_INVERTER") (pin "2") (pinfunction "CAP+_2") (pintype "passive"))
    )
    (net (code "387") (name "Net-(5V_INVERTER-CAP-)") (class "Default")
      (node (ref "150uF_0") (pin "1") (pinfunction "1_1") (pintype "passive"))
      (node (ref "5V_INVERTER") (pin "4") (pinfunction "CAP-_4") (pintype "passive"))
    )
    (net (code "388") (name "unconnected-(5V_INVERTER-BOOST-Pad1)") (class "Default")
      (node (ref "5V_INVERTER") (pin "1") (pinfunction "BOOST_1") (pintype "passive"))
    )
    (net (code "389") (name "unconnected-(5V_INVERTER-OSC-Pad7)") (class "Default")
      (node (ref "5V_INVERTER") (pin "7") (pinfunction "OSC_7") (pintype "passive"))
    )
  )
)
